# lt1241-bare.net
KiCad netlist of a schematic drawn in EAGLE
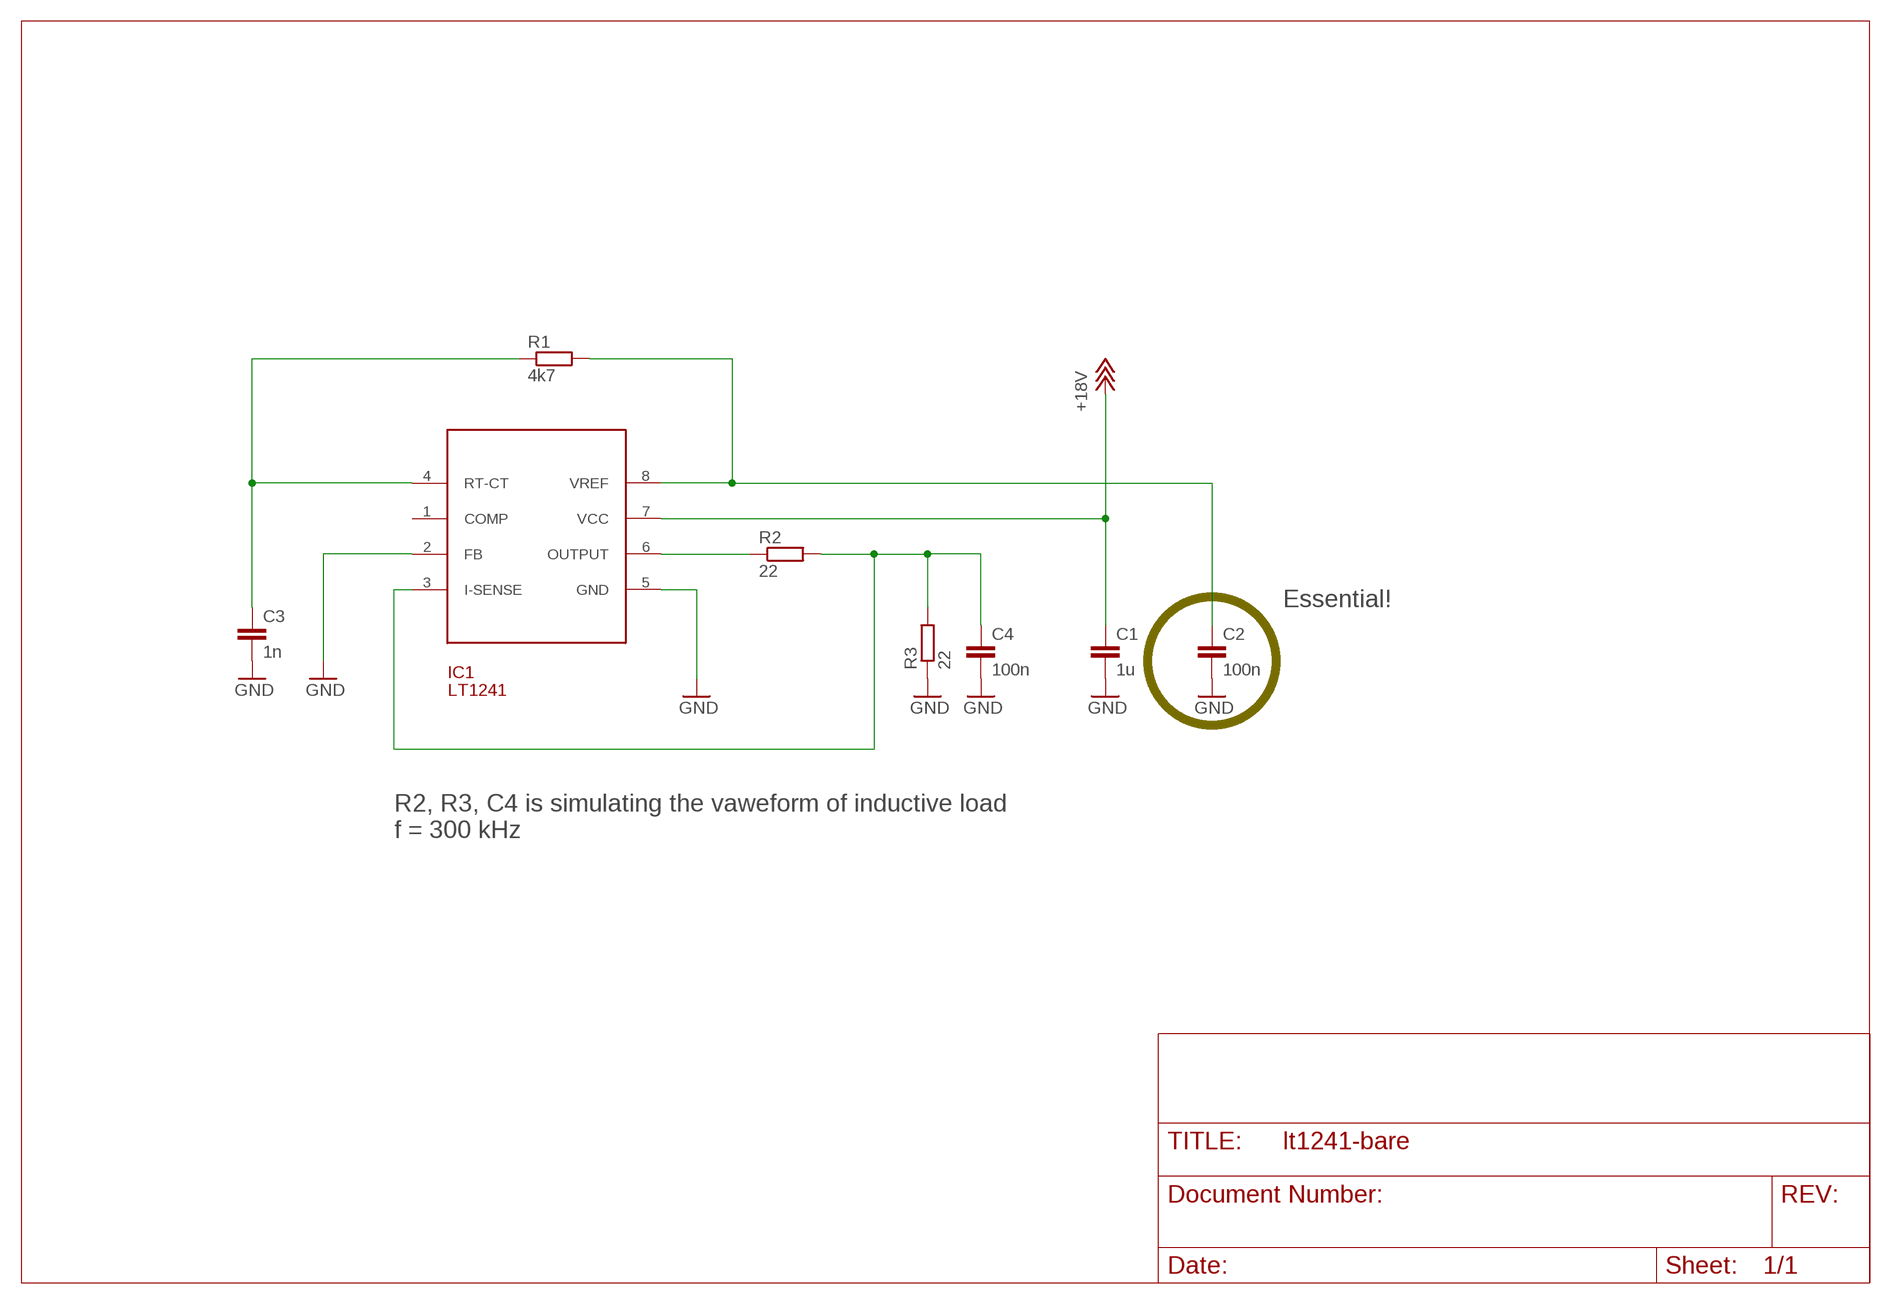
[diagram p0: schematic, sheet 1]

(export (version "E")
  (design (tool "Eeschema 10.0.6"))
  (components
    (comp (ref "C1")
      (value "1u")
      (footprint "eagle-import:C0805")
      (libsource (lib "eagle-import") (part "C-EUC0805"))
    )
    (comp (ref "C2")
      (value "100n")
      (footprint "eagle-import:C0805")
      (libsource (lib "eagle-import") (part "C-EUC0805"))
    )
    (comp (ref "C3")
      (value "1n")
      (footprint "eagle-import:C0805")
      (libsource (lib "eagle-import") (part "C-EUC0805"))
    )
    (comp (ref "C4")
      (value "100n")
      (footprint "eagle-import:C0805")
      (libsource (lib "eagle-import") (part "C-EUC0805"))
    )
    (comp (ref "IC1")
      (value "LT1241")
      (footprint "eagle-import:S8")
      (libsource (lib "eagle-import") (part "LT124X"))
    )
    (comp (ref "R1")
      (value "4k7")
      (footprint "eagle-import:R0805")
      (libsource (lib "eagle-import") (part "R-EU_R0805"))
    )
    (comp (ref "R2")
      (value "22")
      (footprint "eagle-import:R0805")
      (libsource (lib "eagle-import") (part "R-EU_R0805"))
    )
    (comp (ref "R3")
      (value "22")
      (footprint "eagle-import:R0805")
      (libsource (lib "eagle-import") (part "R-EU_R0805"))
    )
  )
  (nets
    (net (code "1") (name "+18V") (class "Default")
      (node (ref "C1") (pin "1") (pinfunction "1_1") (pintype "passive"))
      (node (ref "IC1") (pin "7") (pinfunction "VCC_7") (pintype "bidirectional"))
    )
    (net (code "2") (name "GND") (class "Default")
      (node (ref "C1") (pin "2") (pinfunction "2_2") (pintype "passive"))
      (node (ref "C2") (pin "2") (pinfunction "2_2") (pintype "passive"))
      (node (ref "C3") (pin "2") (pinfunction "2_2") (pintype "passive"))
      (node (ref "C4") (pin "2") (pinfunction "2_2") (pintype "passive"))
      (node (ref "IC1") (pin "2") (pinfunction "FB_2") (pintype "bidirectional"))
      (node (ref "IC1") (pin "5") (pinfunction "GND_5") (pintype "bidirectional"))
      (node (ref "R3") (pin "1") (pinfunction "1_1") (pintype "passive"))
    )
    (net (code "3") (name "Net-(IC1-I-SENSE)") (class "Default")
      (node (ref "C4") (pin "1") (pinfunction "1_1") (pintype "passive"))
      (node (ref "IC1") (pin "3") (pinfunction "I-SENSE_3") (pintype "bidirectional"))
      (node (ref "R2") (pin "2") (pinfunction "2_2") (pintype "passive"))
      (node (ref "R3") (pin "2") (pinfunction "2_2") (pintype "passive"))
    )
    (net (code "4") (name "Net-(IC1-OUTPUT)") (class "Default")
      (node (ref "IC1") (pin "6") (pinfunction "OUTPUT_6") (pintype "bidirectional"))
      (node (ref "R2") (pin "1") (pinfunction "1_1") (pintype "passive"))
    )
    (net (code "5") (name "Net-(IC1-RT-CT)") (class "Default")
      (node (ref "C3") (pin "1") (pinfunction "1_1") (pintype "passive"))
      (node (ref "IC1") (pin "4") (pinfunction "RT-CT_4") (pintype "bidirectional"))
      (node (ref "R1") (pin "1") (pinfunction "1_1") (pintype "passive"))
    )
    (net (code "6") (name "Net-(IC1-VREF)") (class "Default")
      (node (ref "C2") (pin "1") (pinfunction "1_1") (pintype "passive"))
      (node (ref "IC1") (pin "8") (pinfunction "VREF_8") (pintype "bidirectional"))
      (node (ref "R1") (pin "2") (pinfunction "2_2") (pintype "passive"))
    )
    (net (code "7") (name "unconnected-(IC1-COMP-Pad1)") (class "Default")
      (node (ref "IC1") (pin "1") (pinfunction "COMP_1") (pintype "bidirectional"))
    )
  )
)
